# Overview.net
KiCad netlist of a schematic drawn in Altium Designer
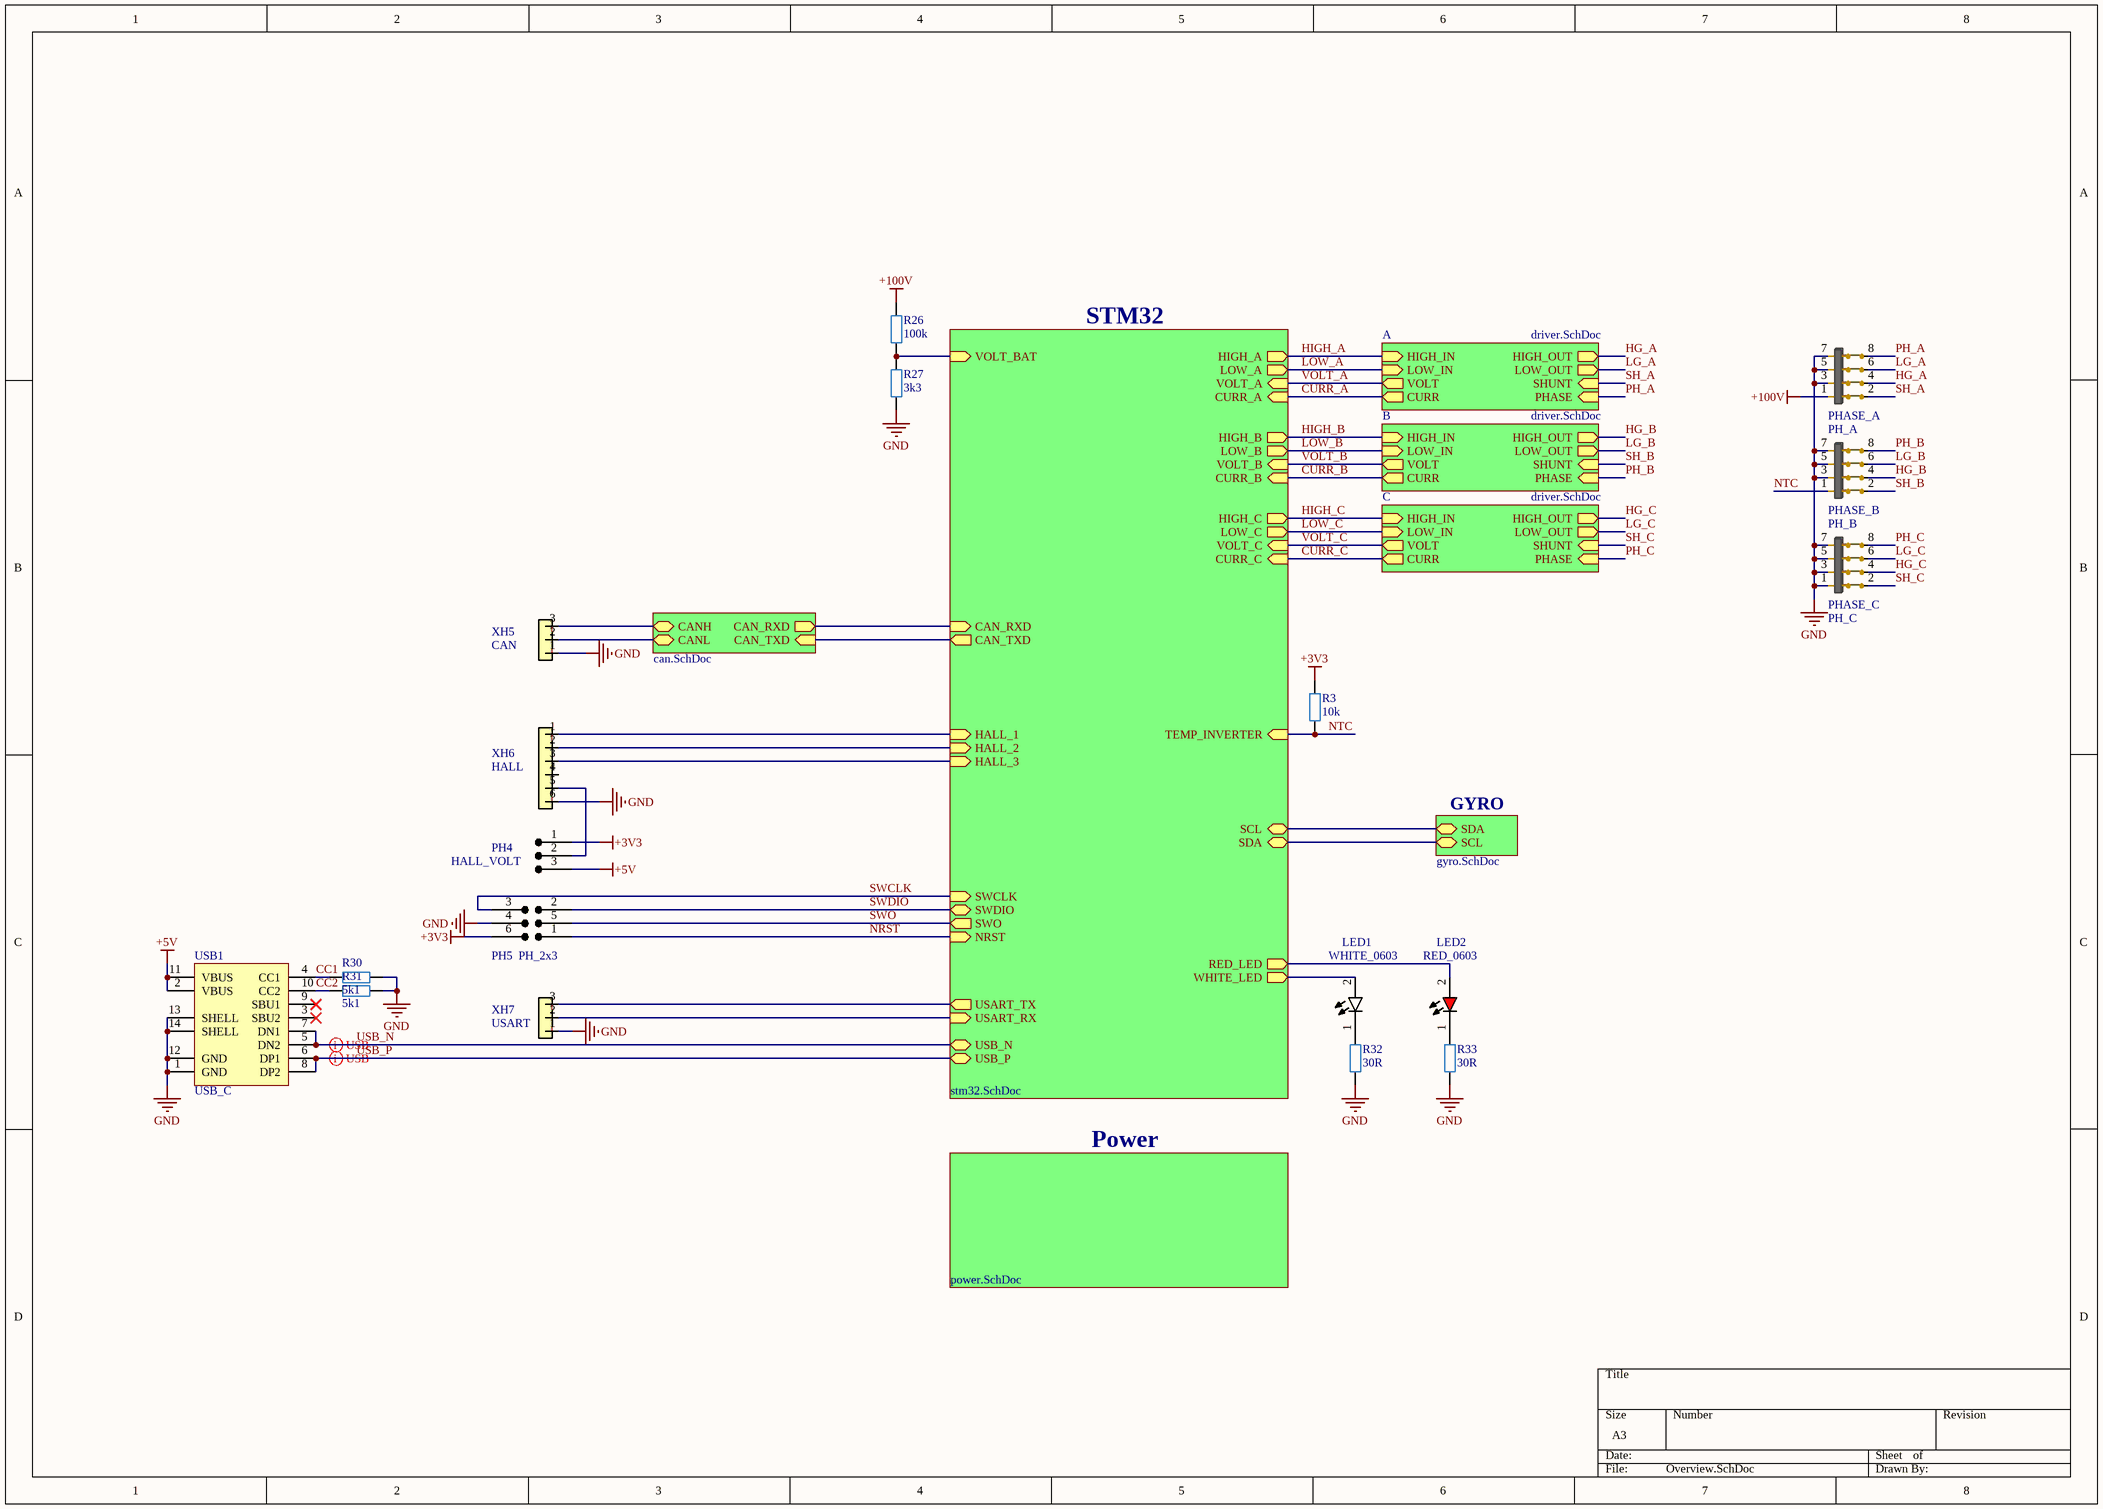
[diagram p0: Overview.SchDoc]

(export (version "E")
  (design (tool "Eeschema 10.0.6"))
  (components
    (comp (ref "LED1")
      (value "WHITE_0603")
      (footprint "WHITE_0603")
      (fields (field (name "MFR.") "XINGLIGHT") (field (name "MFR. PART") "XL-1608WWC-06"))
      (libsource (lib "LED") (part "WHITE_0603"))
    )
    (comp (ref "LED2")
      (value "RED_0603")
      (footprint "RED_0603")
      (fields (field (name "MFR.") "XINGLIGHT") (field (name "MFR. PART") "XL-1608SURC-06"))
      (libsource (lib "LED") (part "RED_0603"))
    )
    (comp (ref "PH4")
      (value "HALL_VOLT")
      (footprint "PH_1x3")
      (description "2.54mm Pin Headers")
      (fields (field (name "MFR. PART") "2.54-1*3P") (field (name "MFR.") "BOOMELE(Boom Precision Elec)"))
      (libsource (lib "Connectors") (part "PH_1x3"))
    )
    (comp (ref "PH5")
      (value "PH_2x3")
      (footprint "PH_2x3")
      (description "2.54mm Pin Headers")
      (libsource (lib "Connectors") (part "PH_2x3"))
    )
    (comp (ref "PH_A")
      (value "PHASE_A")
      (footprint "PH_2x4_M")
      (fields (field (name "MFR. PART") "PH2.54-07-04PWS") (field (name "MFR.") "XUNPU"))
      (libsource (lib "Connectors") (part "PH_2x4_M"))
    )
    (comp (ref "PH_B")
      (value "PHASE_B")
      (footprint "PH_2x4_M")
      (fields (field (name "MFR. PART") "PH2.54-07-04PWS") (field (name "MFR.") "XUNPU"))
      (libsource (lib "Connectors") (part "PH_2x4_M"))
    )
    (comp (ref "PH_C")
      (value "PHASE_C")
      (footprint "PH_2x4_M")
      (fields (field (name "MFR. PART") "PH2.54-07-04PWS") (field (name "MFR.") "XUNPU"))
      (libsource (lib "Connectors") (part "PH_2x4_M"))
    )
    (comp (ref "R3")
      (value "10k")
      (footprint "RES_0603")
      (description "100mW Thick Film Resistors")
      (libsource (lib "Passive") (part "RES_0603"))
    )
    (comp (ref "R26")
      (value "100k")
      (footprint "RES_0603")
      (description "100mW Thick Film Resistors")
      (libsource (lib "Passive") (part "RES_0603"))
    )
    (comp (ref "R27")
      (value "3k3")
      (footprint "RES_0603")
      (description "100mW Thick Film Resistors")
      (libsource (lib "Passive") (part "RES_0603"))
    )
    (comp (ref "R30")
      (value "5k1")
      (footprint "RES_0603")
      (description "100mW Thick Film Resistors")
      (libsource (lib "Passive") (part "RES_0603"))
    )
    (comp (ref "R31")
      (value "5k1")
      (footprint "RES_0603")
      (description "100mW Thick Film Resistors")
      (libsource (lib "Passive") (part "RES_0603"))
    )
    (comp (ref "R32")
      (value "30R")
      (footprint "RES_0603")
      (description "100mW Thick Film Resistors")
      (libsource (lib "Passive") (part "RES_0603"))
    )
    (comp (ref "R33")
      (value "30R")
      (footprint "RES_0603")
      (description "100mW Thick Film Resistors")
      (libsource (lib "Passive") (part "RES_0603"))
    )
    (comp (ref "USB1")
      (value "USB_C")
      (footprint "USB_C")
      (fields (field (name "MFR. PART") "TYPE-C 16PIN 2MD(073)") (field (name "MFR.") "SHOU HAN"))
      (libsource (lib "Connectors") (part "USB_C"))
    )
    (comp (ref "XH5")
      (value "CAN")
      (footprint "XY-XHB2.54-3A21")
      (description "1x3P 3P 1 2.54mm 2.54mm 3 -25℃~+85℃ 2A Bend-in Push-Pull,P=2.54mm Wire To Board Connector ROHS")
      (fields (field (name "MFR. PART") "XY-XHB2.54-3A21") (field (name "MFR.") "XYECONN"))
      (libsource (lib "Connectors") (part "XY-XHB2.54-3A21"))
    )
    (comp (ref "XH6")
      (value "HALL")
      (footprint "XY-XHB2.54-6A21")
      (description "1x6P 6P 1 2.54mm 2.54mm 6 -25℃~+85℃ 2A Bend-in Push-Pull,P=2.54mm Wire To Board Connector ROHS")
      (fields (field (name "MFR. PART") "XY-XHB2.54-6A21") (field (name "MFR.") "XYECONN"))
      (libsource (lib "Connectors") (part "XY-XHB2.54-6A21"))
    )
    (comp (ref "XH7")
      (value "USART")
      (footprint "XY-XHB2.54-3A21")
      (description "1x3P 3P 1 2.54mm 2.54mm 3 -25℃~+85℃ 2A Bend-in Push-Pull,P=2.54mm Wire To Board Connector ROHS")
      (fields (field (name "MFR. PART") "XY-XHB2.54-3A21") (field (name "MFR.") "XYECONN"))
      (libsource (lib "Connectors") (part "XY-XHB2.54-3A21"))
    )
  )
  (nets
    (net (code "1") (name "+3V3") (class "Default")
      (node (ref "PH4") (pin "1") (pinfunction "1_1") (pintype "passive"))
      (node (ref "PH5") (pin "6") (pinfunction "6_6") (pintype "passive"))
      (node (ref "R3") (pin "2") (pintype "passive"))
    )
    (net (code "2") (name "+5V") (class "Default")
      (node (ref "PH4") (pin "3") (pinfunction "3_3") (pintype "passive"))
      (node (ref "USB1") (pin "11") (pinfunction "VBUS_11") (pintype "passive"))
      (node (ref "USB1") (pin "2") (pinfunction "VBUS_2") (pintype "passive"))
    )
    (net (code "3") (name "+100V") (class "Default")
      (node (ref "PH_A") (pin "1") (pinfunction "1_1") (pintype "passive"))
      (node (ref "R26") (pin "2") (pintype "passive"))
    )
    (net (code "4") (name "/CANH") (class "Default") (node (ref "XH5") (pin "3") (pintype "passive")))
    (net (code "5") (name "/CANL") (class "Default") (node (ref "XH5") (pin "2") (pintype "passive")))
    (net (code "8") (name "/CC1") (class "Default")
      (node (ref "R30") (pin "1") (pintype "passive"))
      (node (ref "USB1") (pin "4") (pinfunction "CC1_4") (pintype "passive"))
    )
    (net (code "9") (name "/CC2") (class "Default")
      (node (ref "R31") (pin "1") (pintype "passive"))
      (node (ref "USB1") (pin "10") (pinfunction "CC2_10") (pintype "passive"))
    )
    (net (code "13") (name "/HALL_1") (class "Default") (node (ref "XH6") (pin "1") (pintype "passive")))
    (net (code "14") (name "/HALL_2") (class "Default") (node (ref "XH6") (pin "2") (pintype "passive")))
    (net (code "15") (name "/HALL_3") (class "Default") (node (ref "XH6") (pin "3") (pintype "passive")))
    (net (code "16") (name "/HG_A") (class "Default")
      (node (ref "PH_A") (pin "4") (pinfunction "4_4") (pintype "passive"))
    )
    (net (code "17") (name "/HG_B") (class "Default")
      (node (ref "PH_B") (pin "4") (pinfunction "4_4") (pintype "passive"))
    )
    (net (code "18") (name "/HG_C") (class "Default")
      (node (ref "PH_C") (pin "4") (pinfunction "4_4") (pintype "passive"))
    )
    (net (code "22") (name "/LG_A") (class "Default")
      (node (ref "PH_A") (pin "6") (pinfunction "6_6") (pintype "passive"))
    )
    (net (code "23") (name "/LG_B") (class "Default")
      (node (ref "PH_B") (pin "6") (pinfunction "6_6") (pintype "passive"))
    )
    (net (code "24") (name "/LG_C") (class "Default")
      (node (ref "PH_C") (pin "6") (pinfunction "6_6") (pintype "passive"))
    )
    (net (code "28") (name "/NRST") (class "Default")
      (node (ref "PH5") (pin "1") (pinfunction "1_1") (pintype "passive"))
    )
    (net (code "29") (name "/NTC") (class "Default")
      (node (ref "PH_B") (pin "1") (pinfunction "1_1") (pintype "passive"))
      (node (ref "R3") (pin "1") (pintype "passive"))
    )
    (net (code "30") (name "/PH_A") (class "Default")
      (node (ref "PH_A") (pin "8") (pinfunction "8_8") (pintype "passive"))
    )
    (net (code "31") (name "/PH_B") (class "Default")
      (node (ref "PH_B") (pin "8") (pinfunction "8_8") (pintype "passive"))
    )
    (net (code "32") (name "/PH_C") (class "Default")
      (node (ref "PH_C") (pin "8") (pinfunction "8_8") (pintype "passive"))
    )
    (net (code "33") (name "/RED_LED") (class "Default")
      (node (ref "LED2") (pin "2") (pinfunction "A_2") (pintype "passive"))
    )
    (net (code "36") (name "/SH_A") (class "Default")
      (node (ref "PH_A") (pin "2") (pinfunction "2_2") (pintype "passive"))
    )
    (net (code "37") (name "/SH_B") (class "Default")
      (node (ref "PH_B") (pin "2") (pinfunction "2_2") (pintype "passive"))
    )
    (net (code "38") (name "/SH_C") (class "Default")
      (node (ref "PH_C") (pin "2") (pinfunction "2_2") (pintype "passive"))
    )
    (net (code "39") (name "/SWCLK") (class "Default")
      (node (ref "PH5") (pin "3") (pinfunction "3_3") (pintype "passive"))
    )
    (net (code "40") (name "/SWDIO") (class "Default")
      (node (ref "PH5") (pin "2") (pinfunction "2_2") (pintype "passive"))
    )
    (net (code "41") (name "/SWO") (class "Default")
      (node (ref "PH5") (pin "5") (pinfunction "5_5") (pintype "passive"))
    )
    (net (code "42") (name "/USART_RX") (class "Default") (node (ref "XH7") (pin "2") (pintype "passive")))
    (net (code "43") (name "/USART_TX") (class "Default") (node (ref "XH7") (pin "3") (pintype "passive")))
    (net (code "44") (name "/USB_N") (class "Default")
      (node (ref "USB1") (pin "5") (pinfunction "DN2_5") (pintype "passive"))
      (node (ref "USB1") (pin "7") (pinfunction "DN1_7") (pintype "passive"))
    )
    (net (code "45") (name "/USB_P") (class "Default")
      (node (ref "USB1") (pin "6") (pinfunction "DP1_6") (pintype "passive"))
      (node (ref "USB1") (pin "8") (pinfunction "DP2_8") (pintype "passive"))
    )
    (net (code "48") (name "/VOLT_BAT") (class "Default")
      (node (ref "R26") (pin "1") (pintype "passive"))
      (node (ref "R27") (pin "2") (pintype "passive"))
    )
    (net (code "50") (name "/WHITE_LED") (class "Default")
      (node (ref "LED1") (pin "2") (pinfunction "A_2") (pintype "passive"))
    )
    (net (code "51") (name "GND") (class "Default")
      (node (ref "PH5") (pin "4") (pinfunction "4_4") (pintype "passive"))
      (node (ref "PH_A") (pin "3") (pinfunction "3_3") (pintype "passive"))
      (node (ref "PH_A") (pin "5") (pinfunction "5_5") (pintype "passive"))
      (node (ref "PH_A") (pin "7") (pinfunction "7_7") (pintype "passive"))
      (node (ref "PH_B") (pin "3") (pinfunction "3_3") (pintype "passive"))
      (node (ref "PH_B") (pin "5") (pinfunction "5_5") (pintype "passive"))
      (node (ref "PH_B") (pin "7") (pinfunction "7_7") (pintype "passive"))
      (node (ref "PH_C") (pin "1") (pinfunction "1_1") (pintype "passive"))
      (node (ref "PH_C") (pin "3") (pinfunction "3_3") (pintype "passive"))
      (node (ref "PH_C") (pin "5") (pinfunction "5_5") (pintype "passive"))
      (node (ref "PH_C") (pin "7") (pinfunction "7_7") (pintype "passive"))
      (node (ref "R27") (pin "1") (pintype "passive"))
      (node (ref "R30") (pin "2") (pintype "passive"))
      (node (ref "R31") (pin "2") (pintype "passive"))
      (node (ref "R32") (pin "1") (pintype "passive"))
      (node (ref "R33") (pin "1") (pintype "passive"))
      (node (ref "USB1") (pin "1") (pinfunction "GND_1") (pintype "passive"))
      (node (ref "USB1") (pin "12") (pinfunction "GND_12") (pintype "passive"))
      (node (ref "USB1") (pin "13") (pinfunction "SHELL_13") (pintype "passive"))
      (node (ref "USB1") (pin "14") (pinfunction "SHELL_14") (pintype "passive"))
      (node (ref "XH5") (pin "1") (pintype "passive"))
      (node (ref "XH6") (pin "6") (pinfunction "6_6") (pintype "passive"))
      (node (ref "XH7") (pin "1") (pintype "passive"))
    )
    (net (code "52") (name "Net-(LED1-K)") (class "Default")
      (node (ref "LED1") (pin "1") (pinfunction "K_1") (pintype "passive"))
      (node (ref "R32") (pin "2") (pintype "passive"))
    )
    (net (code "53") (name "Net-(LED2-K)") (class "Default")
      (node (ref "LED2") (pin "1") (pinfunction "K_1") (pintype "passive"))
      (node (ref "R33") (pin "2") (pintype "passive"))
    )
    (net (code "54") (name "Net-(PH4-Pad2)") (class "Default")
      (node (ref "PH4") (pin "2") (pinfunction "2_2") (pintype "passive"))
      (node (ref "XH6") (pin "5") (pinfunction "5_5") (pintype "passive"))
    )
    (net (code "55") (name "unconnected-(USB1-SBU1-Pad9)") (class "Default")
      (node (ref "USB1") (pin "9") (pinfunction "SBU1_9") (pintype "passive+no_connect"))
    )
    (net (code "56") (name "unconnected-(USB1-SBU2-Pad3)") (class "Default")
      (node (ref "USB1") (pin "3") (pinfunction "SBU2_3") (pintype "passive+no_connect"))
    )
    (net (code "57") (name "unconnected-(XH6-Pad4)") (class "Default")
      (node (ref "XH6") (pin "4") (pinfunction "4_4") (pintype "passive"))
    )
  )
)
